# design.net
KiCad netlist of a schematic drawn in EasyEDA Pro
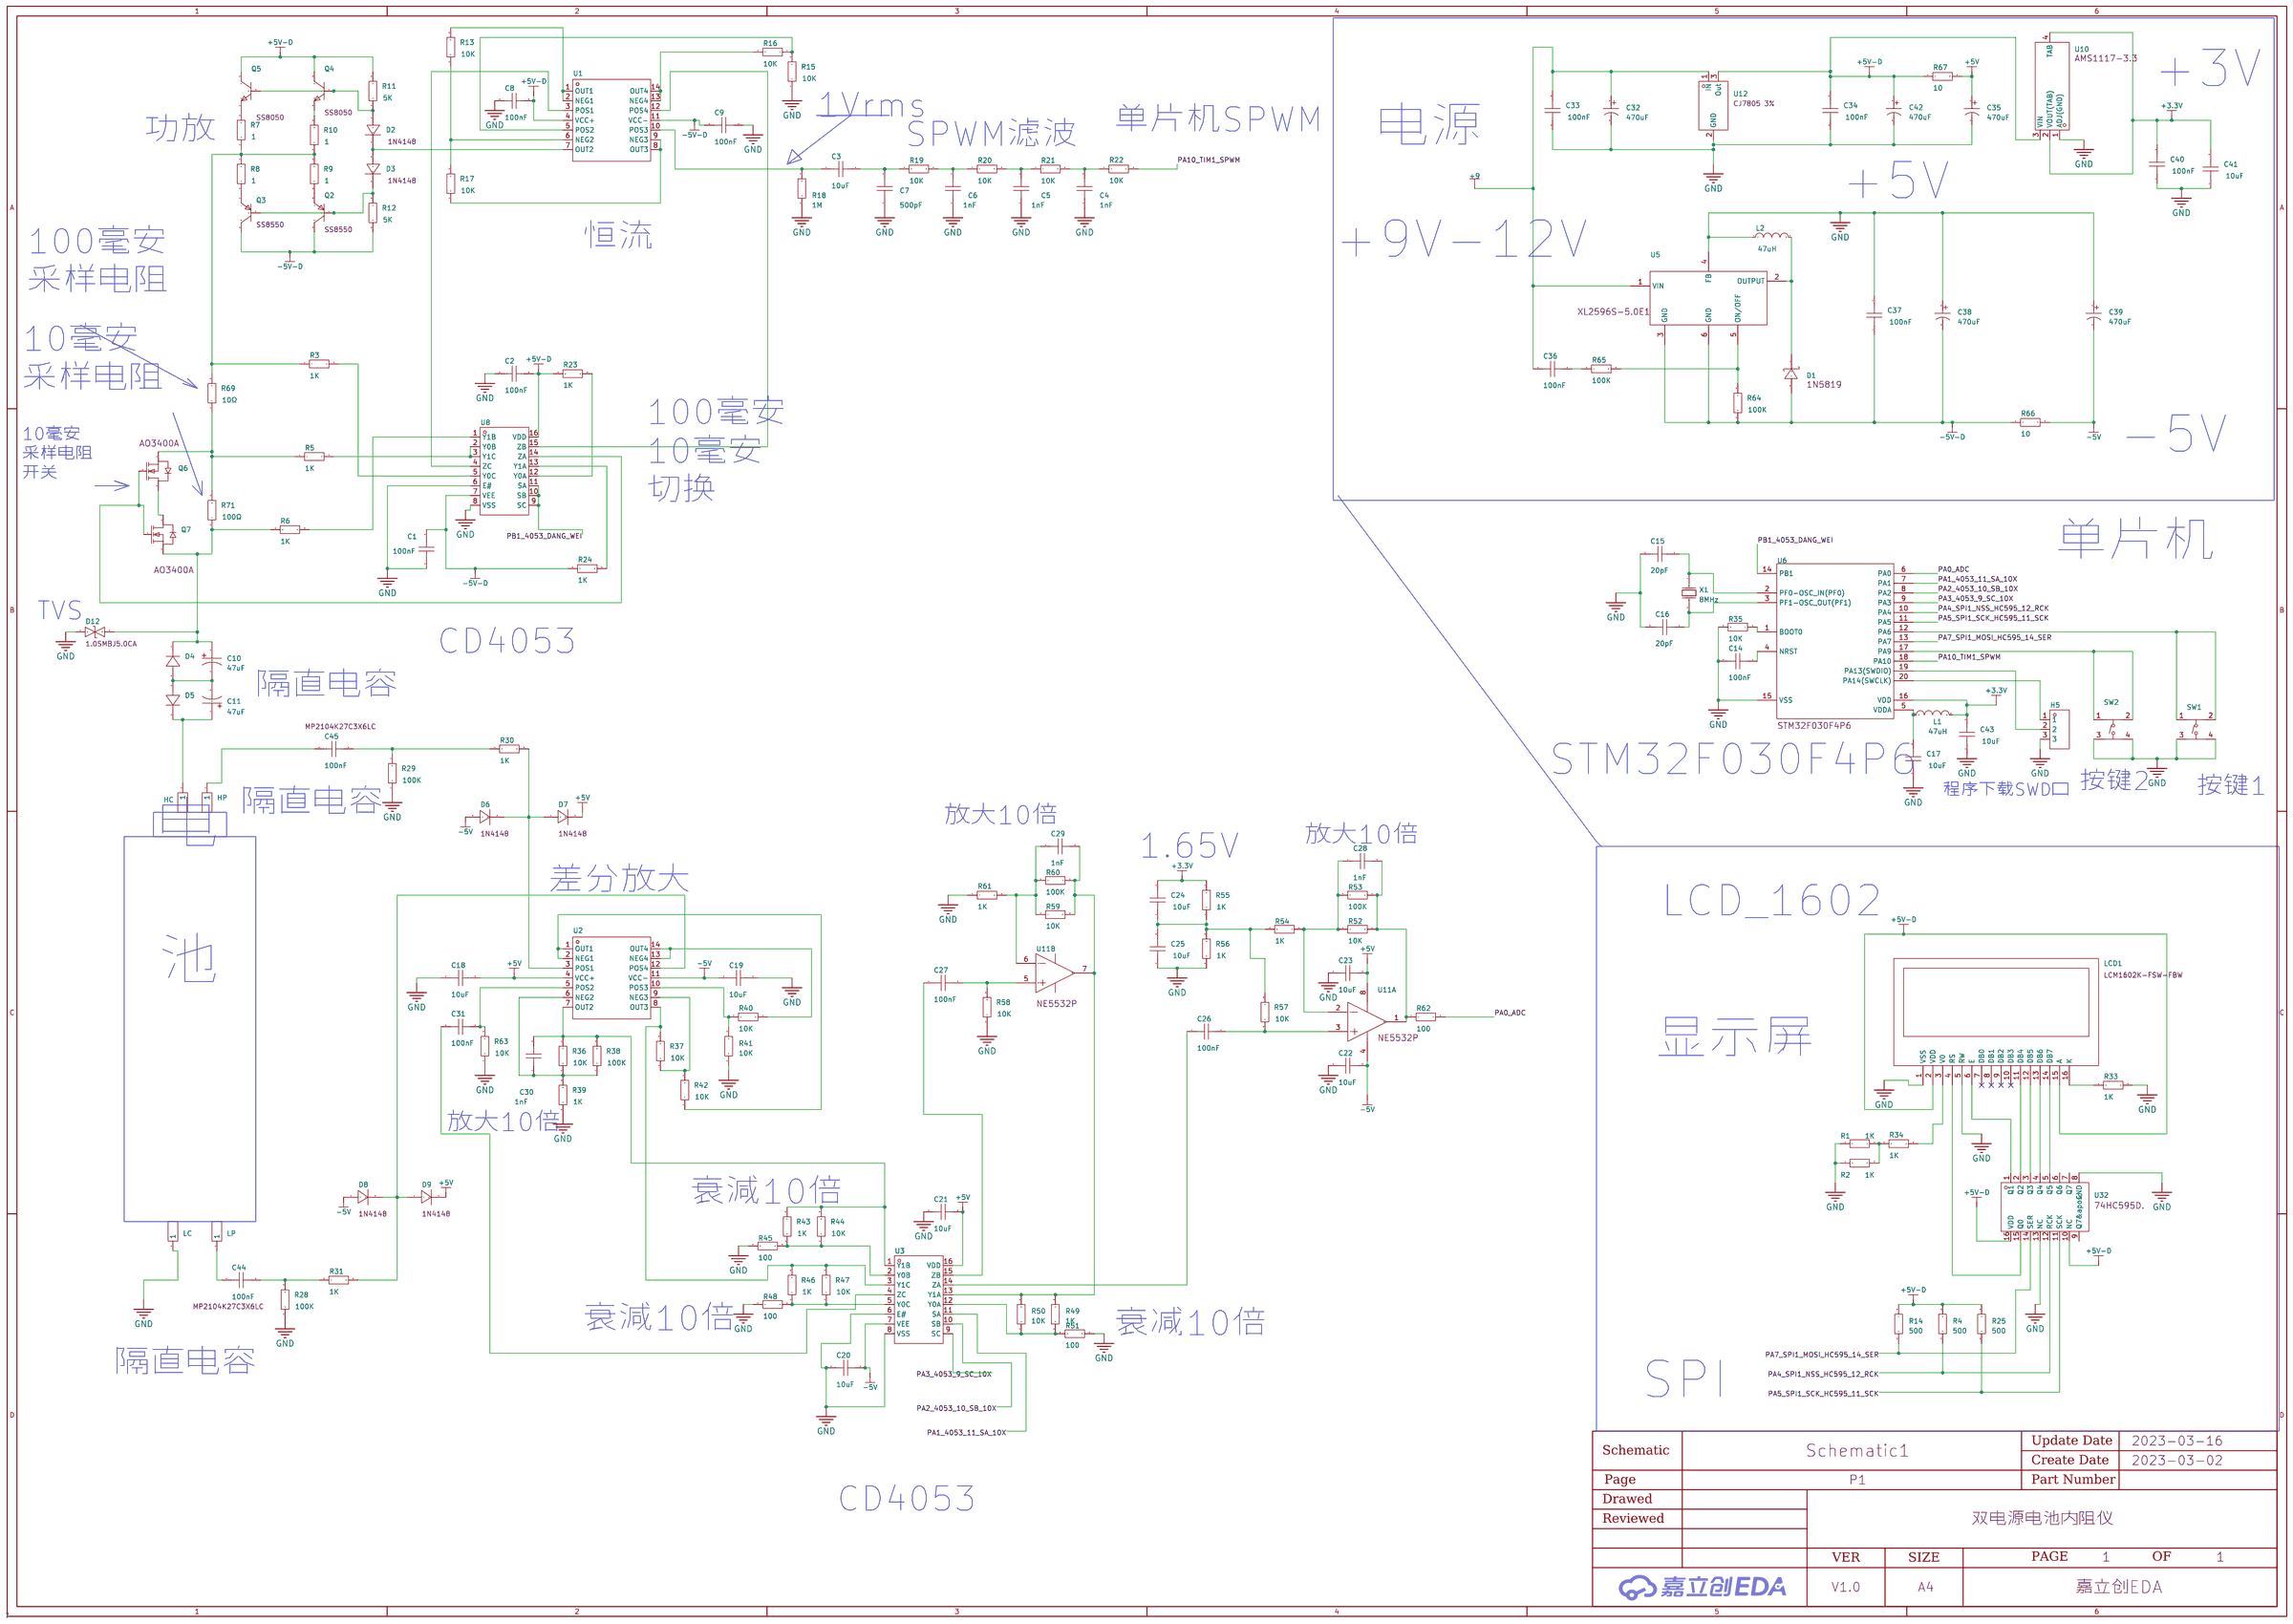
[diagram p0: schematic sheet]

(export (version "E")
  (design (tool "Eeschema 10.0.6"))
  (components
    (comp (ref "C1")
      (value "100nF")
      (footprint "easyedapro:C0603")
      (libsource (lib "easyedapro") (part "CapAcitance"))
    )
    (comp (ref "C2")
      (value "100nF")
      (footprint "easyedapro:C0603")
      (libsource (lib "easyedapro") (part "CapAcitance"))
    )
    (comp (ref "C3")
      (value "10uF")
      (footprint "easyedapro:C0603")
      (libsource (lib "easyedapro") (part "CapAcitance"))
    )
    (comp (ref "C4")
      (value "1nF")
      (footprint "easyedapro:C0603")
      (libsource (lib "easyedapro") (part "CapAcitance"))
    )
    (comp (ref "C5")
      (value "1nF")
      (footprint "easyedapro:C0603")
      (libsource (lib "easyedapro") (part "CapAcitance"))
    )
    (comp (ref "C6")
      (value "1nF")
      (footprint "easyedapro:C0603")
      (libsource (lib "easyedapro") (part "CapAcitance"))
    )
    (comp (ref "C7")
      (value "500pF")
      (footprint "easyedapro:C0603")
      (libsource (lib "easyedapro") (part "CapAcitance"))
    )
    (comp (ref "C8")
      (value "100nF")
      (footprint "easyedapro:C0603")
      (libsource (lib "easyedapro") (part "CapAcitance"))
    )
    (comp (ref "C9")
      (value "100nF")
      (footprint "easyedapro:C0603")
      (libsource (lib "easyedapro") (part "CapAcitance"))
    )
    (comp (ref "C10")
      (value "47uF")
      (footprint "easyedapro:CAP-TH_BD10.0-P5.00-D1.0-FD")
      (description "容值:47uF;精度:±20%;额定电压:200V;电容体直径:10mm;电容体长度:20mm;脚间距:5mm;工作寿命:5000hrs@105℃;")
      (fields (field (name "Manufacturer Part") "KF470M200G200A") (field (name "Manufacturer") "CapXon(丰宾)"))
      (libsource (lib "easyedapro") (part "KF470M200G200A"))
    )
    (comp (ref "C11")
      (value "47uF")
      (footprint "easyedapro:CAP-TH_BD10.0-P5.00-D1.0-FD")
      (description "容值:47uF;精度:±20%;额定电压:200V;电容体直径:10mm;电容体长度:20mm;脚间距:5mm;工作寿命:5000hrs@105℃;")
      (fields (field (name "Manufacturer Part") "KF470M200G200A") (field (name "Manufacturer") "CapXon(丰宾)"))
      (libsource (lib "easyedapro") (part "KF470M200G200A"))
    )
    (comp (ref "C14")
      (value "100nF")
      (footprint "easyedapro:C0603")
      (libsource (lib "easyedapro") (part "CapAcitance"))
    )
    (comp (ref "C15")
      (value "20pF")
      (footprint "easyedapro:C0603")
      (libsource (lib "easyedapro") (part "CapAcitance"))
    )
    (comp (ref "C16")
      (value "20pF")
      (footprint "easyedapro:C0603")
      (libsource (lib "easyedapro") (part "CapAcitance"))
    )
    (comp (ref "C17")
      (value "10uF")
      (footprint "easyedapro:C0603")
      (libsource (lib "easyedapro") (part "CapAcitance"))
    )
    (comp (ref "C18")
      (value "10uF")
      (footprint "easyedapro:C0603")
      (libsource (lib "easyedapro") (part "CapAcitance"))
    )
    (comp (ref "C19")
      (value "10uF")
      (footprint "easyedapro:C0603")
      (libsource (lib "easyedapro") (part "CapAcitance"))
    )
    (comp (ref "C20")
      (value "10uF")
      (footprint "easyedapro:C0603")
      (libsource (lib "easyedapro") (part "CapAcitance"))
    )
    (comp (ref "C21")
      (value "10uF")
      (footprint "easyedapro:C0603")
      (libsource (lib "easyedapro") (part "CapAcitance"))
    )
    (comp (ref "C22")
      (value "10uF")
      (footprint "easyedapro:C0603")
      (libsource (lib "easyedapro") (part "CapAcitance"))
    )
    (comp (ref "C23")
      (value "10uF")
      (footprint "easyedapro:C0603")
      (libsource (lib "easyedapro") (part "CapAcitance"))
    )
    (comp (ref "C24")
      (value "10uF")
      (footprint "easyedapro:C0603")
      (libsource (lib "easyedapro") (part "CapAcitance"))
    )
    (comp (ref "C25")
      (value "10uF")
      (footprint "easyedapro:C0603")
      (libsource (lib "easyedapro") (part "CapAcitance"))
    )
    (comp (ref "C26")
      (value "100nF")
      (footprint "easyedapro:C0603")
      (libsource (lib "easyedapro") (part "CapAcitance"))
    )
    (comp (ref "C27")
      (value "100nF")
      (footprint "easyedapro:C0603")
      (libsource (lib "easyedapro") (part "CapAcitance"))
    )
    (comp (ref "C28")
      (value "1nF")
      (footprint "easyedapro:C0603")
      (libsource (lib "easyedapro") (part "CapAcitance"))
    )
    (comp (ref "C29")
      (value "1nF")
      (footprint "easyedapro:C0603")
      (libsource (lib "easyedapro") (part "CapAcitance"))
    )
    (comp (ref "C30")
      (value "1nF")
      (footprint "easyedapro:C0603")
      (libsource (lib "easyedapro") (part "CapAcitance"))
    )
    (comp (ref "C31")
      (value "100nF")
      (footprint "easyedapro:C0603")
      (libsource (lib "easyedapro") (part "CapAcitance"))
    )
    (comp (ref "C32")
      (value "470uF")
      (footprint "easyedapro:CAP-TH_BD8.0-P3.50-D0.6-FD")
      (description "容值:470uF;精度:±20%;额定电压:16V;电容体直径:8mm;电容体长度:12mm;脚间距:3.5mm;工作寿命:2000hrs@105℃;")
      (fields
        (field (name "Manufacturer Part") "KM477M016F12RR0VH2FP0")
        (field (name "Manufacturer") "CX(承兴)")
      )
      (libsource (lib "easyedapro") (part "470uf16v"))
    )
    (comp (ref "C33")
      (value "100nF")
      (footprint "easyedapro:C0603")
      (libsource (lib "easyedapro") (part "CapAcitance"))
    )
    (comp (ref "C34")
      (value "100nF")
      (footprint "easyedapro:C0603")
      (libsource (lib "easyedapro") (part "CapAcitance"))
    )
    (comp (ref "C35")
      (value "470uF")
      (footprint "easyedapro:CAP-TH_BD8.0-P3.50-D0.6-FD")
      (description "容值:470uF;精度:±20%;额定电压:16V;电容体直径:8mm;电容体长度:12mm;脚间距:3.5mm;工作寿命:2000hrs@105℃;")
      (fields
        (field (name "Manufacturer Part") "KM477M016F12RR0VH2FP0")
        (field (name "Manufacturer") "CX(承兴)")
      )
      (libsource (lib "easyedapro") (part "470uf16v"))
    )
    (comp (ref "C36")
      (value "100nF")
      (footprint "easyedapro:C0603")
      (libsource (lib "easyedapro") (part "CapAcitance"))
    )
    (comp (ref "C37")
      (value "100nF")
      (footprint "easyedapro:C0603")
      (libsource (lib "easyedapro") (part "CapAcitance"))
    )
    (comp (ref "C38")
      (value "470uF")
      (footprint "easyedapro:CAP-TH_BD8.0-P3.50-D0.6-FD")
      (description "容值:470uF;精度:±20%;额定电压:16V;电容体直径:8mm;电容体长度:12mm;脚间距:3.5mm;工作寿命:2000hrs@105℃;")
      (fields
        (field (name "Manufacturer Part") "KM477M016F12RR0VH2FP0")
        (field (name "Manufacturer") "CX(承兴)")
      )
      (libsource (lib "easyedapro") (part "470uf16v"))
    )
    (comp (ref "C39")
      (value "470uF")
      (footprint "easyedapro:CAP-TH_BD8.0-P3.50-D0.6-FD")
      (description "容值:470uF;精度:±20%;额定电压:16V;电容体直径:8mm;电容体长度:12mm;脚间距:3.5mm;工作寿命:2000hrs@105℃;")
      (fields
        (field (name "Manufacturer Part") "KM477M016F12RR0VH2FP0")
        (field (name "Manufacturer") "CX(承兴)")
      )
      (libsource (lib "easyedapro") (part "470uf16v"))
    )
    (comp (ref "C40")
      (value "100nF")
      (footprint "easyedapro:C0603")
      (libsource (lib "easyedapro") (part "CapAcitance"))
    )
    (comp (ref "C41")
      (value "10uF")
      (footprint "easyedapro:C0603")
      (libsource (lib "easyedapro") (part "CapAcitance"))
    )
    (comp (ref "C42")
      (value "470uF")
      (footprint "easyedapro:CAP-TH_BD8.0-P3.50-D0.6-FD")
      (description "容值:470uF;精度:±20%;额定电压:16V;电容体直径:8mm;电容体长度:12mm;脚间距:3.5mm;工作寿命:2000hrs@105℃;")
      (fields
        (field (name "Manufacturer Part") "KM477M016F12RR0VH2FP0")
        (field (name "Manufacturer") "CX(承兴)")
      )
      (libsource (lib "easyedapro") (part "470uf16v"))
    )
    (comp (ref "C43")
      (value "10uF")
      (footprint "easyedapro:C0603")
      (libsource (lib "easyedapro") (part "CapAcitance"))
    )
    (comp (ref "C44")
      (value "100nF")
      (footprint "easyedapro:CAP-TH_L13.0-W6.0-P10.00-D1.0")
      (description "等级:X2;容值:100nF;精度:±10%;")
      (fields (field (name "Manufacturer Part") "MP2104K27C3X6LC") (field (name "Manufacturer") "SRD(圣融达)"))
      (libsource (lib "easyedapro") (part "MP2104KGC3XLC"))
    )
    (comp (ref "C45")
      (value "100nF")
      (footprint "easyedapro:CAP-TH_L13.0-W6.0-P10.00-D1.0")
      (description "等级:X2;容值:100nF;精度:±10%;")
      (fields (field (name "Manufacturer Part") "MP2104K27C3X6LC") (field (name "Manufacturer") "SRD(圣融达)"))
      (libsource (lib "easyedapro") (part "MP2104KGC3XLC"))
    )
    (comp (ref "D1")
      (value "1N5819")
      (footprint "easyedapro:SMA_L4.4-W2.6-LS5.0-RD")
      (description "直流反向耐压(Vr):40V;平均整流电流(Io):1A;正向压降(Vf):500mV@1A;")
      (fields (field (name "Manufacturer Part") "1N5819") (field (name "Manufacturer") "KEXIN(科信)"))
      (libsource (lib "easyedapro") (part "1N5819_C437199"))
    )
    (comp (ref "D2")
      (value "1N4148")
      (footprint "easyedapro:DO-35_BD2.0-L4.0-P8.00-D0.5-FD")
      (fields (field (name "Manufacturer Part") "1N4148") (field (name "Manufacturer") "ST(先科)"))
      (libsource (lib "easyedapro") (part "1N4148"))
    )
    (comp (ref "D3")
      (value "1N4148")
      (footprint "easyedapro:DO-35_BD2.0-L4.0-P8.00-D0.5-FD")
      (fields (field (name "Manufacturer Part") "1N4148") (field (name "Manufacturer") "ST(先科)"))
      (libsource (lib "easyedapro") (part "1N4148"))
    )
    (comp (ref "D4")
      (value "~")
      (footprint "easyedapro:DO_1N4007")
      (libsource (lib "easyedapro") (part "D_1N4007"))
    )
    (comp (ref "D5")
      (value "~")
      (footprint "easyedapro:DO_1N4007")
      (libsource (lib "easyedapro") (part "D_1N4007"))
    )
    (comp (ref "D6")
      (value "1N4148")
      (footprint "easyedapro:DO-35_BD2.0-L4.0-P8.00-D0.5-FD")
      (fields (field (name "Manufacturer Part") "1N4148") (field (name "Manufacturer") "ST(先科)"))
      (libsource (lib "easyedapro") (part "1N4148"))
    )
    (comp (ref "D7")
      (value "1N4148")
      (footprint "easyedapro:DO-35_BD2.0-L4.0-P8.00-D0.5-FD")
      (fields (field (name "Manufacturer Part") "1N4148") (field (name "Manufacturer") "ST(先科)"))
      (libsource (lib "easyedapro") (part "1N4148"))
    )
    (comp (ref "D8")
      (value "1N4148")
      (footprint "easyedapro:DO-35_BD2.0-L4.0-P8.00-D0.5-FD")
      (fields (field (name "Manufacturer Part") "1N4148") (field (name "Manufacturer") "ST(先科)"))
      (libsource (lib "easyedapro") (part "1N4148"))
    )
    (comp (ref "D9")
      (value "1N4148")
      (footprint "easyedapro:DO-35_BD2.0-L4.0-P8.00-D0.5-FD")
      (fields (field (name "Manufacturer Part") "1N4148") (field (name "Manufacturer") "ST(先科)"))
      (libsource (lib "easyedapro") (part "1N4148"))
    )
    (comp (ref "D12")
      (value "1.0SMBJ5.0CA")
      (footprint "easyedapro:SMB_L4.6-W3.6-LS5.3-BI")
      (description "极性:双向;反向截止电压(Vrwm):5V;击穿电压:6.4V;峰值脉冲电流(Ipp)@10/1000s:108.7A;最大钳位电压:9.2V;")
      (fields (field (name "Manufacturer Part") "1.0SMBJ5.0CA") (field (name "Manufacturer") "BORN(伯恩半导体)"))
      (libsource (lib "easyedapro") (part "1.0SMBJ5.0CA"))
    )
    (comp (ref "H5")
      (value "~")
      (footprint "easyedapro:HDR-TH_3P-P2.54-V-M")
      (libsource (lib "easyedapro") (part "PZ254V-11-03P_C2937625"))
    )
    (comp (ref "HC")
      (value "~")
      (footprint "easyedapro:HDR-TH_1P-V-M_XKB_X4611WV-01I-C28D40")
      (libsource (lib "easyedapro") (part "HDR_1x1"))
    )
    (comp (ref "HP")
      (value "~")
      (footprint "easyedapro:HDR-TH_1P-V-M_XKB_X4611WV-01I-C28D40")
      (libsource (lib "easyedapro") (part "HDR_1x1"))
    )
    (comp (ref "L1")
      (value "47uH")
      (footprint "easyedapro:IND-SMD_L4.5-W4.0_SLF0403")
      (description "电感值:47uH;直流电阻(DCR):844mΩ;精度:±10%;额定电流:540mA;")
      (fields
        (field (name "Manufacturer Part") "SLF0403-470KTT")
        (field (name "Manufacturer") "Sunltech(韩国顺磁)")
      )
      (libsource (lib "easyedapro") (part "SLF0403-470KTT"))
    )
    (comp (ref "L2")
      (value "47uH")
      (footprint "easyedapro:IND-SMD_L4.5-W4.0_SLF0403")
      (description "电感值:47uH;直流电阻(DCR):844mΩ;精度:±10%;额定电流:540mA;")
      (fields
        (field (name "Manufacturer Part") "SLF0403-470KTT")
        (field (name "Manufacturer") "Sunltech(韩国顺磁)")
      )
      (libsource (lib "easyedapro") (part "SLF0403-470KTT"))
    )
    (comp (ref "LC")
      (value "~")
      (footprint "easyedapro:HDR-TH_1P-V-M_XKB_X4611WV-01I-C28D40")
      (libsource (lib "easyedapro") (part "HDR_1x1"))
    )
    (comp (ref "LCD1")
      (value "LCM1602K-FSW-FBW")
      (footprint "easyedapro:MODULE-TH_LCM1602K")
      (description "尺寸(inch):-;主控芯片:KS0066U;")
      (fields
        (field (name "Manufacturer Part") "LCM1602K-FSW-FBW")
        (field (name "Manufacturer") "LONTECH(厦门龙特)")
      )
      (libsource (lib "easyedapro") (part "LCM1602K-FSW-FBW"))
    )
    (comp (ref "LP")
      (value "~")
      (footprint "easyedapro:HDR-TH_1P-V-M_XKB_X4611WV-01I-C28D40")
      (libsource (lib "easyedapro") (part "HDR_1x1"))
    )
    (comp (ref "Q2")
      (value "SS8550")
      (footprint "easyedapro:SOT-23-3_L2.9-W1.6-P1.90-LS2.8-BR")
      (fields (field (name "Manufacturer Part") "SS8550") (field (name "Manufacturer") "ElecSuper(静芯微）"))
      (libsource (lib "easyedapro") (part "SS8550_C5249677"))
    )
    (comp (ref "Q3")
      (value "SS8550")
      (footprint "easyedapro:SOT-23-3_L2.9-W1.6-P1.90-LS2.8-BR")
      (fields (field (name "Manufacturer Part") "SS8550") (field (name "Manufacturer") "ElecSuper(静芯微）"))
      (libsource (lib "easyedapro") (part "SS8550_C5249677"))
    )
    (comp (ref "Q4")
      (value "SS8050")
      (footprint "easyedapro:SOT-23-3_L2.9-W1.6-P1.90-LS2.8-BR")
      (fields (field (name "Manufacturer Part") "SS8050") (field (name "Manufacturer") "ElecSuper(静芯微）"))
      (libsource (lib "easyedapro") (part "SS8050_C5249676"))
    )
    (comp (ref "Q5")
      (value "SS8050")
      (footprint "easyedapro:SOT-23-3_L2.9-W1.6-P1.90-LS2.8-BR")
      (fields (field (name "Manufacturer Part") "SS8050") (field (name "Manufacturer") "ElecSuper(静芯微）"))
      (libsource (lib "easyedapro") (part "SS8050_C5249676"))
    )
    (comp (ref "Q6")
      (value "AO3400A")
      (footprint "easyedapro:SOT-23-3_L2.9-W1.3-P1.90-LS2.4-BR")
      (fields (field (name "Manufacturer Part") "AO3400A") (field (name "Manufacturer") "UMW(广东友台半导体)"))
      (libsource (lib "easyedapro") (part "AO3400A_C347475"))
    )
    (comp (ref "Q7")
      (value "AO3400A")
      (footprint "easyedapro:SOT-23-3_L2.9-W1.3-P1.90-LS2.4-BR")
      (fields (field (name "Manufacturer Part") "AO3400A") (field (name "Manufacturer") "UMW(广东友台半导体)"))
      (libsource (lib "easyedapro") (part "AO3400A_C347475"))
    )
    (comp (ref "R1")
      (value "1K")
      (footprint "easyedapro:Res_1/8W")
      (libsource (lib "easyedapro") (part "电阻"))
    )
    (comp (ref "R2")
      (value "1K")
      (footprint "easyedapro:Res_1/8W")
      (libsource (lib "easyedapro") (part "电阻"))
    )
    (comp (ref "R3")
      (value "1K")
      (footprint "easyedapro:Res_1/8W")
      (libsource (lib "easyedapro") (part "电阻"))
    )
    (comp (ref "R4")
      (value "500")
      (footprint "easyedapro:Res_1/8W")
      (libsource (lib "easyedapro") (part "电阻"))
    )
    (comp (ref "R5")
      (value "1K")
      (footprint "easyedapro:Res_1/8W")
      (libsource (lib "easyedapro") (part "电阻"))
    )
    (comp (ref "R6")
      (value "1K")
      (footprint "easyedapro:Res_1/8W")
      (libsource (lib "easyedapro") (part "电阻"))
    )
    (comp (ref "R7") (value "1") (footprint "easyedapro:Res_1/8W") (libsource (lib "easyedapro") (part "电阻")))
    (comp (ref "R8") (value "1") (footprint "easyedapro:Res_1/8W") (libsource (lib "easyedapro") (part "电阻")))
    (comp (ref "R9") (value "1") (footprint "easyedapro:Res_1/8W") (libsource (lib "easyedapro") (part "电阻")))
    (comp (ref "R10")
      (value "1")
      (footprint "easyedapro:Res_1/8W")
      (libsource (lib "easyedapro") (part "电阻"))
    )
    (comp (ref "R11")
      (value "5K")
      (footprint "easyedapro:Res_1/8W")
      (libsource (lib "easyedapro") (part "电阻"))
    )
    (comp (ref "R12")
      (value "5K")
      (footprint "easyedapro:Res_1/8W")
      (libsource (lib "easyedapro") (part "电阻"))
    )
    (comp (ref "R13")
      (value "10K")
      (footprint "easyedapro:Res_1/8W")
      (libsource (lib "easyedapro") (part "电阻"))
    )
    (comp (ref "R14")
      (value "500")
      (footprint "easyedapro:Res_1/8W")
      (libsource (lib "easyedapro") (part "电阻"))
    )
    (comp (ref "R15")
      (value "10K")
      (footprint "easyedapro:Res_1/8W")
      (libsource (lib "easyedapro") (part "电阻"))
    )
    (comp (ref "R16")
      (value "10K")
      (footprint "easyedapro:Res_1/8W")
      (libsource (lib "easyedapro") (part "电阻"))
    )
    (comp (ref "R17")
      (value "10K")
      (footprint "easyedapro:Res_1/8W")
      (libsource (lib "easyedapro") (part "电阻"))
    )
    (comp (ref "R18")
      (value "1M")
      (footprint "easyedapro:Res_1/8W")
      (libsource (lib "easyedapro") (part "电阻"))
    )
    (comp (ref "R19")
      (value "10K")
      (footprint "easyedapro:Res_1/8W")
      (libsource (lib "easyedapro") (part "电阻"))
    )
    (comp (ref "R20")
      (value "10K")
      (footprint "easyedapro:Res_1/8W")
      (libsource (lib "easyedapro") (part "电阻"))
    )
    (comp (ref "R21")
      (value "10K")
      (footprint "easyedapro:Res_1/8W")
      (libsource (lib "easyedapro") (part "电阻"))
    )
    (comp (ref "R22")
      (value "10K")
      (footprint "easyedapro:Res_1/8W")
      (libsource (lib "easyedapro") (part "电阻"))
    )
    (comp (ref "R23")
      (value "1K")
      (footprint "easyedapro:Res_1/8W")
      (libsource (lib "easyedapro") (part "电阻"))
    )
    (comp (ref "R24")
      (value "1K")
      (footprint "easyedapro:Res_1/8W")
      (libsource (lib "easyedapro") (part "电阻"))
    )
    (comp (ref "R25")
      (value "500")
      (footprint "easyedapro:Res_1/8W")
      (libsource (lib "easyedapro") (part "电阻"))
    )
    (comp (ref "R28")
      (value "100K")
      (footprint "easyedapro:Res_1/8W")
      (libsource (lib "easyedapro") (part "电阻"))
    )
    (comp (ref "R29")
      (value "100K")
      (footprint "easyedapro:Res_1/8W")
      (libsource (lib "easyedapro") (part "电阻"))
    )
    (comp (ref "R30")
      (value "1K")
      (footprint "easyedapro:Res_1/8W")
      (libsource (lib "easyedapro") (part "电阻"))
    )
    (comp (ref "R31")
      (value "1K")
      (footprint "easyedapro:Res_1/8W")
      (libsource (lib "easyedapro") (part "电阻"))
    )
    (comp (ref "R33")
      (value "1K")
      (footprint "easyedapro:Res_1/8W")
      (libsource (lib "easyedapro") (part "电阻"))
    )
    (comp (ref "R34")
      (value "1K")
      (footprint "easyedapro:Res_1/8W")
      (libsource (lib "easyedapro") (part "电阻"))
    )
    (comp (ref "R35")
      (value "10K")
      (footprint "easyedapro:Res_1/8W")
      (libsource (lib "easyedapro") (part "电阻"))
    )
    (comp (ref "R36")
      (value "10K")
      (footprint "easyedapro:Res_1/8W")
      (libsource (lib "easyedapro") (part "电阻"))
    )
    (comp (ref "R37")
      (value "10K")
      (footprint "easyedapro:Res_1/8W")
      (libsource (lib "easyedapro") (part "电阻"))
    )
    (comp (ref "R38")
      (value "100K")
      (footprint "easyedapro:Res_1/8W")
      (libsource (lib "easyedapro") (part "电阻"))
    )
    (comp (ref "R39")
      (value "1K")
      (footprint "easyedapro:Res_1/8W")
      (libsource (lib "easyedapro") (part "电阻"))
    )
    (comp (ref "R40")
      (value "10K")
      (footprint "easyedapro:Res_1/8W")
      (libsource (lib "easyedapro") (part "电阻"))
    )
    (comp (ref "R41")
      (value "10K")
      (footprint "easyedapro:Res_1/8W")
      (libsource (lib "easyedapro") (part "电阻"))
    )
    (comp (ref "R42")
      (value "10K")
      (footprint "easyedapro:Res_1/8W")
      (libsource (lib "easyedapro") (part "电阻"))
    )
    (comp (ref "R43")
      (value "1K")
      (footprint "easyedapro:Res_1/8W")
      (libsource (lib "easyedapro") (part "电阻"))
    )
    (comp (ref "R44")
      (value "10K")
      (footprint "easyedapro:Res_1/8W")
      (libsource (lib "easyedapro") (part "电阻"))
    )
    (comp (ref "R45")
      (value "100")
      (footprint "easyedapro:Res_1/8W")
      (libsource (lib "easyedapro") (part "电阻"))
    )
    (comp (ref "R46")
      (value "1K")
      (footprint "easyedapro:Res_1/8W")
      (libsource (lib "easyedapro") (part "电阻"))
    )
    (comp (ref "R47")
      (value "10K")
      (footprint "easyedapro:Res_1/8W")
      (libsource (lib "easyedapro") (part "电阻"))
    )
    (comp (ref "R48")
      (value "100")
      (footprint "easyedapro:Res_1/8W")
      (libsource (lib "easyedapro") (part "电阻"))
    )
    (comp (ref "R49")
      (value "1K")
      (footprint "easyedapro:Res_1/8W")
      (libsource (lib "easyedapro") (part "电阻"))
    )
    (comp (ref "R50")
      (value "10K")
      (footprint "easyedapro:Res_1/8W")
      (libsource (lib "easyedapro") (part "电阻"))
    )
    (comp (ref "R51")
      (value "100")
      (footprint "easyedapro:Res_1/8W")
      (libsource (lib "easyedapro") (part "电阻"))
    )
    (comp (ref "R52")
      (value "10K")
      (footprint "easyedapro:Res_1/8W")
      (libsource (lib "easyedapro") (part "电阻"))
    )
    (comp (ref "R53")
      (value "100K")
      (footprint "easyedapro:Res_1/8W")
      (libsource (lib "easyedapro") (part "电阻"))
    )
    (comp (ref "R54")
      (value "1K")
      (footprint "easyedapro:Res_1/8W")
      (libsource (lib "easyedapro") (part "电阻"))
    )
    (comp (ref "R55")
      (value "1K")
      (footprint "easyedapro:Res_1/8W")
      (libsource (lib "easyedapro") (part "电阻"))
    )
    (comp (ref "R56")
      (value "1K")
      (footprint "easyedapro:Res_1/8W")
      (libsource (lib "easyedapro") (part "电阻"))
    )
    (comp (ref "R57")
      (value "10K")
      (footprint "easyedapro:Res_1/8W")
      (libsource (lib "easyedapro") (part "电阻"))
    )
    (comp (ref "R58")
      (value "10K")
      (footprint "easyedapro:Res_1/8W")
      (libsource (lib "easyedapro") (part "电阻"))
    )
    (comp (ref "R59")
      (value "10K")
      (footprint "easyedapro:Res_1/8W")
      (libsource (lib "easyedapro") (part "电阻"))
    )
    (comp (ref "R60")
      (value "100K")
      (footprint "easyedapro:Res_1/8W")
      (libsource (lib "easyedapro") (part "电阻"))
    )
    (comp (ref "R61")
      (value "1K")
      (footprint "easyedapro:Res_1/8W")
      (libsource (lib "easyedapro") (part "电阻"))
    )
    (comp (ref "R62")
      (value "100")
      (footprint "easyedapro:Res_1/8W")
      (libsource (lib "easyedapro") (part "电阻"))
    )
    (comp (ref "R63")
      (value "10K")
      (footprint "easyedapro:Res_1/8W")
      (libsource (lib "easyedapro") (part "电阻"))
    )
    (comp (ref "R64")
      (value "100K")
      (footprint "easyedapro:Res_1/8W")
      (libsource (lib "easyedapro") (part "电阻"))
    )
    (comp (ref "R65")
      (value "100K")
      (footprint "easyedapro:Res_1/8W")
      (libsource (lib "easyedapro") (part "电阻"))
    )
    (comp (ref "R66") (value "10") (footprint "easyedapro:R0603") (libsource (lib "easyedapro") (part "电阻")))
    (comp (ref "R67") (value "10") (footprint "easyedapro:R0603") (libsource (lib "easyedapro") (part "电阻")))
    (comp (ref "R69")
      (value "10Ω")
      (footprint "easyedapro:R2512")
      (description "电阻类型:厚膜电阻;阻值:10Ω;精度:±5%;功率:2W;温度系数:±200ppm/℃;最大工作电压:200V;工作温度范围:-55℃~+155℃;")
      (fields (field (name "Manufacturer Part") "RC2512JK-7W10RL") (field (name "Manufacturer") "YAGEO(国巨)"))
      (libsource (lib "easyedapro") (part "RC2512JK-7W10RL"))
    )
    (comp (ref "R71")
      (value "100Ω")
      (footprint "easyedapro:R0603")
      (description "电阻类型:厚膜电阻;阻值:100Ω;精度:±1%;功率:100mW;温度系数:±100ppm/℃;最大工作电压:75V;工作温度范围:-55℃~+155℃;")
      (fields (field (name "Manufacturer Part") "AC0603FR-07100RL") (field (name "Manufacturer") "YAGEO(国巨)"))
      (libsource (lib "easyedapro") (part "AC0603FR-07100RL"))
    )
    (comp (ref "SW1")
      (value "1TS005A-2600-5001")
      (footprint "easyedapro:SW-TH_4P-L6.0-W6.0-P4.50-LS6.5")
      (fields (field (name "Manufacturer") "HYP(鸿源精密)"))
      (libsource (lib "easyedapro") (part "1TS005A-2600-5001"))
    )
    (comp (ref "SW2")
      (value "1TS005A-2600-5001")
      (footprint "easyedapro:SW-TH_4P-L6.0-W6.0-P4.50-LS6.5")
      (fields (field (name "Manufacturer") "HYP(鸿源精密)"))
      (libsource (lib "easyedapro") (part "1TS005A-2600-5001"))
    )
    (comp (ref "U1")
      (value "TL084CN")
      (footprint "easyedapro:DIP-14_L17.8-W10.2-P2.54-BL")
      (description "运放类型:J-FET;放大器组数:4;增益带宽积（GBP）:4MHz;压摆率（SR）:16 V/us;电源电压:6V ~ 36V, ±3V ~ 18V;各通道供电电流:1.4mA;")
      (fields (field (name "Manufacturer") "TI(德州仪器)"))
      (libsource (lib "easyedapro") (part "TL084CN_C54501"))
    )
    (comp (ref "U2")
      (value "TL084CN")
      (footprint "easyedapro:DIP-14_L17.8-W10.2-P2.54-BL")
      (description "运放类型:J-FET;放大器组数:4;增益带宽积（GBP）:4MHz;压摆率（SR）:16 V/us;电源电压:6V ~ 36V, ±3V ~ 18V;各通道供电电流:1.4mA;")
      (fields (field (name "Manufacturer") "TI(德州仪器)"))
      (libsource (lib "easyedapro") (part "TL084CN_C54501"))
    )
    (comp (ref "U3")
      (value "CD4053BM/TR")
      (footprint "easyedapro:SOP-16_L9.9-W3.9-P1.27-LS6.1-BL")
      (fields (field (name "Manufacturer") "HGSEMI(华冠)"))
      (libsource (lib "easyedapro") (part "CD4053BM/TR"))
    )
    (comp (ref "U5")
      (value "XL2596S-5.0E1")
      (footprint "easyedapro:TO-263-5_L10.2-W9.9-P1.70-LS14.4-TL")
      (fields (field (name "Manufacturer Part") "XL2596S-5.0E1") (field (name "Manufacturer") "XLSEMI(芯龙)"))
      (libsource (lib "easyedapro") (part "XL2596S-5.0E1"))
    )
    (comp (ref "U6")
      (value "STM32F030F4P6")
      (footprint "easyedapro:TSSOP-20_L6.5-W4.4-P0.65-LS6.4-BL")
      (fields (field (name "Manufacturer Part") "STM32F030F4P6") (field (name "Manufacturer") "ST(意法半导体)"))
      (libsource (lib "easyedapro") (part "STM32F030F4P6"))
    )
    (comp (ref "U8")
      (value "CD4053BM/TR")
      (footprint "easyedapro:SOP-16_L9.9-W3.9-P1.27-LS6.1-BL")
      (fields (field (name "Manufacturer") "HGSEMI(华冠)"))
      (libsource (lib "easyedapro") (part "CD4053BM/TR"))
    )
    (comp (ref "U10")
      (value "AMS1117-3.3")
      (footprint "easyedapro:SOT-223-4_L6.5-W3.5-P2.30-LS7.0-BR")
      (description "输出类型:固定;输出极性:正;输出通道数:1;最大输入电压:18V;输出电压:3.3V;压差:1.3V@(1A);输出电流:1A;电源纹波抑制比(PSRR):60dB@(120Hz);")
      (fields (field (name "Manufacturer Part") "AMS1117-3.3") (field (name "Manufacturer") "UMW(广东友台半导体)"))
      (libsource (lib "easyedapro") (part "AMS1117-3.3_C347222"))
    )
    (comp (ref "U11")
      (value "NE5532P")
      (footprint "easyedapro:DIP-8_L9.4-W6.4-P2.54-LS9.1-BL")
      (description "运放类型:General Purpose;放大器组数:2;增益带宽积（GBP）:10MHz;压摆率（SR）:9 V/us;电源电压:±5V ~ 15V;各通道供电电流:8mA;")
      (fields (field (name "Manufacturer Part") "NE5532P") (field (name "Manufacturer") "TI(德州仪器)"))
      (libsource (lib "easyedapro") (part "NE5532P"))
    )
    (comp (ref "U12")
      (value "CJ7805 3%")
      (footprint "easyedapro:TO-252-2_L6.6-W6.1-P4.58-LS10.1-BR-CW")
      (description "输出类型:固定;输出极性:正;输出通道数:1;最大输入电压:35V;输出电压:5V;压差:2V@(1A);输出电流:1.5A;")
      (fields (field (name "Manufacturer Part") "CJ7805 3%") (field (name "Manufacturer") "CJ(江苏长电/长晶)"))
      (libsource (lib "easyedapro") (part "CJ7805 3%"))
    )
    (comp (ref "U32")
      (value "74HC595D.")
      (footprint "easyedapro:SOP-16_L9.9-W3.9-P1.27-LS6.0-BL")
      (fields (field (name "Manufacturer Part") "74HC595D.") (field (name "Manufacturer") "FM(富满)"))
      (libsource (lib "easyedapro") (part "74HC595D."))
    )
    (comp (ref "X1")
      (value "8MHz")
      (footprint "easyedapro:OSC-TH_L10.0-W4.5-P5.00")
      (description "晶振类型:49S晶振;频率:8MHz;频率公差:±20ppm;频率稳定度:±30ppm;负载电容:20pF;工作温度:-20℃~+70℃;")
      (fields (field (name "Manufacturer Part") "X49SD8MSD2SC") (field (name "Manufacturer") "YXC(扬兴晶振)"))
      (libsource (lib "easyedapro") (part "X49SD8MSD2SC"))
    )
  )
  (nets
    (net (code "1") (name "+3.3V") (class "Default")
      (node (ref "C24") (pin "2") (pinfunction "2_2") (pintype "input"))
      (node (ref "C40") (pin "2") (pinfunction "2_2") (pintype "input"))
      (node (ref "C41") (pin "2") (pinfunction "2_2") (pintype "input"))
      (node (ref "C43") (pin "2") (pinfunction "2_2") (pintype "input"))
      (node (ref "L1") (pin "2") (pinfunction "2_2") (pintype "input"))
      (node (ref "R55") (pin "2") (pinfunction "2_2") (pintype "input"))
      (node (ref "U10") (pin "2") (pinfunction "VOUT(TAB)_2") (pintype "input"))
      (node (ref "U10") (pin "4") (pinfunction "TAB_4") (pintype "input"))
      (node (ref "U6") (pin "16") (pinfunction "VDD_16") (pintype "input"))
    )
    (net (code "2") (name "+5V") (class "Default")
      (node (ref "C18") (pin "2") (pinfunction "2_2") (pintype "input"))
      (node (ref "C21") (pin "2") (pinfunction "2_2") (pintype "input"))
      (node (ref "C23") (pin "2") (pinfunction "2_2") (pintype "input"))
      (node (ref "C35") (pin "1") (pinfunction "1_1") (pintype "input"))
      (node (ref "D7") (pin "2") (pinfunction "C_2") (pintype "input"))
      (node (ref "D9") (pin "2") (pinfunction "C_2") (pintype "input"))
      (node (ref "R67") (pin "2") (pinfunction "2_2") (pintype "input"))
      (node (ref "U11") (pin "8") (pinfunction "VCC+_8") (pintype "input"))
      (node (ref "U2") (pin "4") (pinfunction "VCC+_4") (pintype "input"))
      (node (ref "U3") (pin "16") (pinfunction "VDD_16") (pintype "input"))
    )
    (net (code "3") (name "+5V-D") (class "Default")
      (node (ref "C2") (pin "2") (pinfunction "2_2") (pintype "input"))
      (node (ref "C34") (pin "2") (pinfunction "2_2") (pintype "input"))
      (node (ref "C42") (pin "1") (pinfunction "1_1") (pintype "input"))
      (node (ref "C8") (pin "2") (pinfunction "2_2") (pintype "input"))
      (node (ref "LCD1") (pin "15") (pinfunction "A_15") (pintype "input"))
      (node (ref "LCD1") (pin "2") (pinfunction "VDD_2") (pintype "input"))
      (node (ref "Q4") (pin "3") (pinfunction "C_3") (pintype "input"))
      (node (ref "Q5") (pin "3") (pinfunction "C_3") (pintype "input"))
      (node (ref "R11") (pin "2") (pinfunction "2_2") (pintype "input"))
      (node (ref "R14") (pin "2") (pinfunction "2_2") (pintype "input"))
      (node (ref "R23") (pin "1") (pinfunction "1_1") (pintype "input"))
      (node (ref "R25") (pin "2") (pinfunction "2_2") (pintype "input"))
      (node (ref "R4") (pin "2") (pinfunction "2_2") (pintype "input"))
      (node (ref "R67") (pin "1") (pinfunction "1_1") (pintype "input"))
      (node (ref "U1") (pin "4") (pinfunction "VCC+_4") (pintype "input"))
      (node (ref "U10") (pin "3") (pinfunction "VIN_3") (pintype "input"))
      (node (ref "U12") (pin "3") (pinfunction "Out_3") (pintype "input"))
      (node (ref "U32") (pin "10") (pinfunction "NC_10") (pintype "input"))
      (node (ref "U32") (pin "16") (pinfunction "VDD_16") (pintype "input"))
      (node (ref "U8") (pin "16") (pinfunction "VDD_16") (pintype "input"))
    )
    (net (code "4") (name "+9") (class "Default")
      (node (ref "C32") (pin "1") (pinfunction "1_1") (pintype "input"))
      (node (ref "C33") (pin "2") (pinfunction "2_2") (pintype "input"))
      (node (ref "C36") (pin "1") (pinfunction "1_1") (pintype "input"))
      (node (ref "U12") (pin "1") (pinfunction "IN_1") (pintype "input"))
      (node (ref "U5") (pin "1") (pinfunction "VIN_1") (pintype "input"))
    )
    (net (code "5") (name "-5V") (class "Default")
      (node (ref "C19") (pin "1") (pinfunction "1_1") (pintype "input"))
      (node (ref "C20") (pin "2") (pinfunction "2_2") (pintype "input"))
      (node (ref "C22") (pin "2") (pinfunction "2_2") (pintype "input"))
      (node (ref "C39") (pin "2") (pinfunction "2_2") (pintype "input"))
      (node (ref "D6") (pin "1") (pinfunction "A_1") (pintype "input"))
      (node (ref "D8") (pin "1") (pinfunction "A_1") (pintype "input"))
      (node (ref "R66") (pin "2") (pinfunction "2_2") (pintype "input"))
      (node (ref "U11") (pin "4") (pinfunction "VCC-_4") (pintype "input"))
      (node (ref "U2") (pin "11") (pinfunction "VCC-_11") (pintype "input"))
      (node (ref "U3") (pin "7") (pinfunction "VEE_7") (pintype "input"))
    )
    (net (code "6") (name "-5V-D") (class "Default")
      (node (ref "C1") (pin "2") (pinfunction "2_2") (pintype "input"))
      (node (ref "C37") (pin "1") (pinfunction "1_1") (pintype "input"))
      (node (ref "C38") (pin "2") (pinfunction "2_2") (pintype "input"))
      (node (ref "C9") (pin "1") (pinfunction "1_1") (pintype "input"))
      (node (ref "D1") (pin "2") (pinfunction "A_2") (pintype "input"))
      (node (ref "Q2") (pin "3") (pinfunction "C_3") (pintype "input"))
      (node (ref "Q3") (pin "3") (pinfunction "C_3") (pintype "input"))
      (node (ref "R12") (pin "1") (pinfunction "1_1") (pintype "input"))
      (node (ref "R24") (pin "1") (pinfunction "1_1") (pintype "input"))
      (node (ref "R64") (pin "1") (pinfunction "1_1") (pintype "input"))
      (node (ref "R66") (pin "1") (pinfunction "1_1") (pintype "input"))
      (node (ref "U1") (pin "11") (pinfunction "VCC-_11") (pintype "input"))
      (node (ref "U5") (pin "3") (pinfunction "GND_3") (pintype "input"))
      (node (ref "U5") (pin "6") (pinfunction "GND_6") (pintype "input"))
      (node (ref "U8") (pin "7") (pinfunction "VEE_7") (pintype "input"))
    )
    (net (code "7") (name "/PA0_ADC") (class "Default")
      (node (ref "R62") (pin "2") (pinfunction "2_2") (pintype "input"))
      (node (ref "U6") (pin "6") (pinfunction "PA0_6") (pintype "bidirectional"))
    )
    (net (code "8") (name "/PA1_4053_11_SA_10X") (class "Default")
      (node (ref "U3") (pin "11") (pinfunction "SA_11") (pintype "input"))
      (node (ref "U6") (pin "7") (pinfunction "PA1_7") (pintype "bidirectional"))
    )
    (net (code "9") (name "/PA2_4053_10_SB_10X") (class "Default")
      (node (ref "U3") (pin "10") (pinfunction "SB_10") (pintype "input"))
      (node (ref "U6") (pin "8") (pinfunction "PA2_8") (pintype "bidirectional"))
    )
    (net (code "10") (name "/PA3_4053_9_SC_10X") (class "Default")
      (node (ref "U3") (pin "9") (pinfunction "SC_9") (pintype "input"))
      (node (ref "U6") (pin "9") (pinfunction "PA3_9") (pintype "bidirectional"))
    )
    (net (code "11") (name "/PA4_SPI1_NSS_HC595_12_RCK") (class "Default")
      (node (ref "R4") (pin "1") (pinfunction "1_1") (pintype "input"))
      (node (ref "U32") (pin "12") (pinfunction "RCK_12") (pintype "input"))
      (node (ref "U6") (pin "10") (pinfunction "PA4_10") (pintype "bidirectional"))
    )
    (net (code "12") (name "/PA5_SPI1_SCK_HC595_11_SCK") (class "Default")
      (node (ref "R25") (pin "1") (pinfunction "1_1") (pintype "input"))
      (node (ref "U32") (pin "11") (pinfunction "SCK_11") (pintype "input"))
      (node (ref "U6") (pin "11") (pinfunction "PA5_11") (pintype "bidirectional"))
    )
    (net (code "13") (name "/PA7_SPI1_MOSI_HC595_14_SER") (class "Default")
      (node (ref "R14") (pin "1") (pinfunction "1_1") (pintype "input"))
      (node (ref "U32") (pin "14") (pinfunction "SER_14") (pintype "input"))
      (node (ref "U6") (pin "13") (pinfunction "PA7_13") (pintype "bidirectional"))
    )
    (net (code "14") (name "/PA10_TIM1_SPWM") (class "Default")
      (node (ref "R22") (pin "2") (pinfunction "2_2") (pintype "input"))
      (node (ref "U6") (pin "18") (pinfunction "PA10_18") (pintype "bidirectional"))
    )
    (net (code "15") (name "/PB1_4053_DANG_WEI") (class "Default")
      (node (ref "U6") (pin "14") (pinfunction "PB1_14") (pintype "bidirectional"))
      (node (ref "U8") (pin "10") (pinfunction "SB_10") (pintype "input"))
      (node (ref "U8") (pin "11") (pinfunction "SA_11") (pintype "input"))
      (node (ref "U8") (pin "9") (pinfunction "SC_9") (pintype "input"))
    )
    (net (code "16") (name "GND") (class "Default")
      (node (ref "C1") (pin "1") (pinfunction "1_1") (pintype "input"))
      (node (ref "C14") (pin "2") (pinfunction "2_2") (pintype "input"))
      (node (ref "C15") (pin "2") (pinfunction "2_2") (pintype "input"))
      (node (ref "C16") (pin "2") (pinfunction "2_2") (pintype "input"))
      (node (ref "C17") (pin "1") (pinfunction "1_1") (pintype "input"))
      (node (ref "C18") (pin "1") (pinfunction "1_1") (pintype "input"))
      (node (ref "C19") (pin "2") (pinfunction "2_2") (pintype "input"))
      (node (ref "C2") (pin "1") (pinfunction "1_1") (pintype "input"))
      (node (ref "C20") (pin "1") (pinfunction "1_1") (pintype "input"))
      (node (ref "C21") (pin "1") (pinfunction "1_1") (pintype "input"))
      (node (ref "C22") (pin "1") (pinfunction "1_1") (pintype "input"))
      (node (ref "C23") (pin "1") (pinfunction "1_1") (pintype "input"))
      (node (ref "C25") (pin "1") (pinfunction "1_1") (pintype "input"))
      (node (ref "C32") (pin "2") (pinfunction "2_2") (pintype "input"))
      (node (ref "C33") (pin "1") (pinfunction "1_1") (pintype "input"))
      (node (ref "C34") (pin "1") (pinfunction "1_1") (pintype "input"))
      (node (ref "C35") (pin "2") (pinfunction "2_2") (pintype "input"))
      (node (ref "C37") (pin "2") (pinfunction "2_2") (pintype "input"))
      (node (ref "C38") (pin "1") (pinfunction "1_1") (pintype "input"))
      (node (ref "C39") (pin "1") (pinfunction "1_1") (pintype "input"))
      (node (ref "C4") (pin "1") (pinfunction "1_1") (pintype "input"))
      (node (ref "C40") (pin "1") (pinfunction "1_1") (pintype "input"))
      (node (ref "C41") (pin "1") (pinfunction "1_1") (pintype "input"))
      (node (ref "C42") (pin "2") (pinfunction "2_2") (pintype "input"))
      (node (ref "C43") (pin "1") (pinfunction "1_1") (pintype "input"))
      (node (ref "C5") (pin "1") (pinfunction "1_1") (pintype "input"))
      (node (ref "C6") (pin "1") (pinfunction "1_1") (pintype "input"))
      (node (ref "C7") (pin "1") (pinfunction "1_1") (pintype "input"))
      (node (ref "C8") (pin "1") (pinfunction "1_1") (pintype "input"))
      (node (ref "C9") (pin "2") (pinfunction "2_2") (pintype "input"))
      (node (ref "D12") (pin "1") (pinfunction "1_1") (pintype "input"))
      (node (ref "H5") (pin "3") (pinfunction "3_3") (pintype "input"))
      (node (ref "L2") (pin "1") (pinfunction "1_1") (pintype "input"))
      (node (ref "LC") (pin "1") (pinfunction "1_1") (pintype "unspecified"))
      (node (ref "LCD1") (pin "1") (pinfunction "VSS_1") (pintype "input"))
      (node (ref "LCD1") (pin "5") (pinfunction "RW_5") (pintype "input"))
      (node (ref "R1") (pin "1") (pinfunction "1_1") (pintype "input"))
      (node (ref "R15") (pin "1") (pinfunction "1_1") (pintype "input"))
      (node (ref "R18") (pin "1") (pinfunction "1_1") (pintype "input"))
      (node (ref "R2") (pin "1") (pinfunction "1_1") (pintype "input"))
      (node (ref "R28") (pin "1") (pinfunction "1_1") (pintype "input"))
      (node (ref "R29") (pin "1") (pinfunction "1_1") (pintype "input"))
      (node (ref "R33") (pin "2") (pinfunction "2_2") (pintype "input"))
      (node (ref "R35") (pin "2") (pinfunction "2_2") (pintype "input"))
      (node (ref "R39") (pin "1") (pinfunction "1_1") (pintype "input"))
      (node (ref "R41") (pin "1") (pinfunction "1_1") (pintype "input"))
      (node (ref "R45") (pin "1") (pinfunction "1_1") (pintype "input"))
      (node (ref "R48") (pin "1") (pinfunction "1_1") (pintype "input"))
      (node (ref "R51") (pin "1") (pinfunction "1_1") (pintype "input"))
      (node (ref "R56") (pin "1") (pinfunction "1_1") (pintype "input"))
      (node (ref "R58") (pin "1") (pinfunction "1_1") (pintype "input"))
      (node (ref "R61") (pin "1") (pinfunction "1_1") (pintype "input"))
      (node (ref "R63") (pin "1") (pinfunction "1_1") (pintype "input"))
      (node (ref "SW1") (pin "3") (pinfunction "3_3") (pintype "input"))
      (node (ref "SW1") (pin "4") (pinfunction "4_4") (pintype "input"))
      (node (ref "SW2") (pin "3") (pinfunction "3_3") (pintype "input"))
      (node (ref "SW2") (pin "4") (pinfunction "4_4") (pintype "input"))
      (node (ref "U10") (pin "1") (pinfunction "ADJ(GND)_1") (pintype "input"))
      (node (ref "U12") (pin "2") (pinfunction "GND_2") (pintype "input"))
      (node (ref "U3") (pin "6") (pinfunction "E#_6") (pintype "input"))
      (node (ref "U3") (pin "8") (pinfunction "VSS_8") (pintype "input"))
      (node (ref "U32") (pin "13") (pinfunction "NC_13") (pintype "input"))
      (node (ref "U32") (pin "8") (pinfunction "GND_8") (pintype "input"))
      (node (ref "U5") (pin "4") (pinfunction "FB_4") (pintype "input"))
      (node (ref "U6") (pin "15") (pinfunction "VSS_15") (pintype "input"))
      (node (ref "U8") (pin "6") (pinfunction "E#_6") (pintype "input"))
      (node (ref "U8") (pin "8") (pinfunction "VSS_8") (pintype "input"))
    )
    (net (code "17") (name "Net-(C3-Pad2)") (class "Default")
      (node (ref "C3") (pin "2") (pinfunction "2_2") (pintype "input"))
      (node (ref "C7") (pin "2") (pinfunction "2_2") (pintype "input"))
      (node (ref "R19") (pin "1") (pinfunction "1_1") (pintype "input"))
    )
    (net (code "18") (name "Net-(C4-Pad2)") (class "Default")
      (node (ref "C4") (pin "2") (pinfunction "2_2") (pintype "input"))
      (node (ref "R21") (pin "2") (pinfunction "2_2") (pintype "input"))
      (node (ref "R22") (pin "1") (pinfunction "1_1") (pintype "input"))
    )
    (net (code "19") (name "Net-(C5-Pad2)") (class "Default")
      (node (ref "C5") (pin "2") (pinfunction "2_2") (pintype "input"))
      (node (ref "R20") (pin "2") (pinfunction "2_2") (pintype "input"))
      (node (ref "R21") (pin "1") (pinfunction "1_1") (pintype "input"))
    )
    (net (code "20") (name "Net-(C6-Pad2)") (class "Default")
      (node (ref "C6") (pin "2") (pinfunction "2_2") (pintype "input"))
      (node (ref "R19") (pin "2") (pinfunction "2_2") (pintype "input"))
      (node (ref "R20") (pin "1") (pinfunction "1_1") (pintype "input"))
    )
    (net (code "21") (name "Net-(C24-Pad1)") (class "Default")
      (node (ref "C24") (pin "1") (pinfunction "1_1") (pintype "input"))
      (node (ref "C25") (pin "2") (pinfunction "2_2") (pintype "input"))
      (node (ref "R54") (pin "2") (pinfunction "2_2") (pintype "input"))
      (node (ref "R55") (pin "1") (pinfunction "1_1") (pintype "input"))
      (node (ref "R56") (pin "2") (pinfunction "2_2") (pintype "input"))
      (node (ref "R57") (pin "2") (pinfunction "2_2") (pintype "input"))
    )
    (net (code "22") (name "Net-(C36-Pad2)") (class "Default")
      (node (ref "C36") (pin "2") (pinfunction "2_2") (pintype "input"))
      (node (ref "R65") (pin "1") (pinfunction "1_1") (pintype "input"))
    )
    (net (code "23") (name "Net-(C44-Pad1)") (class "Default")
      (node (ref "C44") (pin "1") (pinfunction "1_1") (pintype "input"))
      (node (ref "R28") (pin "2") (pinfunction "2_2") (pintype "input"))
      (node (ref "R31") (pin "1") (pinfunction "1_1") (pintype "input"))
    )
    (net (code "24") (name "Net-(C44-Pad2)") (class "Default")
      (node (ref "C44") (pin "2") (pinfunction "2_2") (pintype "input"))
      (node (ref "LP") (pin "1") (pinfunction "1_1") (pintype "unspecified"))
    )
    (net (code "25") (name "Net-(C45-Pad1)") (class "Default")
      (node (ref "C45") (pin "1") (pinfunction "1_1") (pintype "input"))
      (node (ref "R29") (pin "2") (pinfunction "2_2") (pintype "input"))
      (node (ref "R30") (pin "1") (pinfunction "1_1") (pintype "input"))
    )
    (net (code "26") (name "Net-(C45-Pad2)") (class "Default")
      (node (ref "C45") (pin "2") (pinfunction "2_2") (pintype "input"))
      (node (ref "HP") (pin "1") (pinfunction "1_1") (pintype "unspecified"))
    )
    (net (code "27") (name "Net-(D1-C)") (class "Default")
      (node (ref "D1") (pin "1") (pinfunction "C_1") (pintype "input"))
      (node (ref "L2") (pin "2") (pinfunction "2_2") (pintype "input"))
      (node (ref "U5") (pin "2") (pinfunction "OUTPUT_2") (pintype "input"))
    )
    (net (code "28") (name "Net-(D2-A)") (class "Default")
      (node (ref "D2") (pin "1") (pinfunction "A_1") (pintype "input"))
      (node (ref "Q4") (pin "1") (pinfunction "B_1") (pintype "input"))
      (node (ref "Q5") (pin "1") (pinfunction "B_1") (pintype "input"))
      (node (ref "R11") (pin "1") (pinfunction "1_1") (pintype "input"))
    )
    (net (code "29") (name "Net-(D2-C)") (class "Default")
      (node (ref "D2") (pin "2") (pinfunction "C_2") (pintype "input"))
      (node (ref "D3") (pin "1") (pinfunction "A_1") (pintype "input"))
      (node (ref "U1") (pin "7") (pinfunction "OUT2_7") (pintype "input"))
    )
    (net (code "30") (name "Net-(D3-C)") (class "Default")
      (node (ref "D3") (pin "2") (pinfunction "C_2") (pintype "input"))
      (node (ref "Q2") (pin "1") (pinfunction "B_1") (pintype "input"))
      (node (ref "Q3") (pin "1") (pinfunction "B_1") (pintype "input"))
      (node (ref "R12") (pin "2") (pinfunction "2_2") (pintype "input"))
    )
    (net (code "31") (name "Net-(D4-A)") (class "Default")
      (node (ref "C10") (pin "2") (pinfunction "2_2") (pintype "input"))
      (node (ref "C11") (pin "2") (pinfunction "2_2") (pintype "input"))
      (node (ref "D4") (pin "2") (pinfunction "A_2") (pintype "input"))
      (node (ref "D5") (pin "2") (pinfunction "A_2") (pintype "input"))
    )
    (net (code "32") (name "Net-(D4-K)") (class "Default")
      (node (ref "C10") (pin "1") (pinfunction "1_1") (pintype "input"))
      (node (ref "D12") (pin "2") (pinfunction "2_2") (pintype "input"))
      (node (ref "D4") (pin "1") (pinfunction "K_1") (pintype "input"))
      (node (ref "Q7") (pin "2") (pinfunction "S_2") (pintype "input"))
      (node (ref "R6") (pin "1") (pinfunction "1_1") (pintype "input"))
      (node (ref "R71") (pin "1") (pinfunction "1_1") (pintype "input"))
    )
    (net (code "33") (name "Net-(D5-K)") (class "Default")
      (node (ref "C11") (pin "1") (pinfunction "1_1") (pintype "input"))
      (node (ref "D5") (pin "1") (pinfunction "K_1") (pintype "input"))
      (node (ref "HC") (pin "1") (pinfunction "1_1") (pintype "unspecified"))
    )
    (net (code "34") (name "Net-(D6-C)") (class "Default")
      (node (ref "D6") (pin "2") (pinfunction "C_2") (pintype "input"))
      (node (ref "D7") (pin "1") (pinfunction "A_1") (pintype "input"))
      (node (ref "R30") (pin "2") (pinfunction "2_2") (pintype "input"))
      (node (ref "U2") (pin "3") (pinfunction "POS1_3") (pintype "input"))
    )
    (net (code "35") (name "Net-(D8-C)") (class "Default")
      (node (ref "D8") (pin "2") (pinfunction "C_2") (pintype "input"))
      (node (ref "D9") (pin "1") (pinfunction "A_1") (pintype "input"))
      (node (ref "R31") (pin "2") (pinfunction "2_2") (pintype "input"))
      (node (ref "U2") (pin "12") (pinfunction "POS4_12") (pintype "input"))
    )
    (net (code "36") (name "Net-(LCD1-DB4)") (class "Default")
      (node (ref "LCD1") (pin "11") (pinfunction "DB4_11") (pintype "input"))
      (node (ref "U32") (pin "2") (pinfunction "Q2_2") (pintype "input"))
    )
    (net (code "37") (name "Net-(LCD1-DB5)") (class "Default")
      (node (ref "LCD1") (pin "12") (pinfunction "DB5_12") (pintype "input"))
      (node (ref "U32") (pin "3") (pinfunction "Q3_3") (pintype "input"))
    )
    (net (code "38") (name "Net-(LCD1-DB6)") (class "Default")
      (node (ref "LCD1") (pin "13") (pinfunction "DB6_13") (pintype "input"))
      (node (ref "U32") (pin "4") (pinfunction "Q4_4") (pintype "input"))
    )
    (net (code "39") (name "Net-(LCD1-DB7)") (class "Default")
      (node (ref "LCD1") (pin "14") (pinfunction "DB7_14") (pintype "input"))
      (node (ref "U32") (pin "5") (pinfunction "Q5_5") (pintype "input"))
    )
    (net (code "40") (name "Net-(LCD1-E)") (class "Default")
      (node (ref "LCD1") (pin "6") (pinfunction "E_6") (pintype "input"))
      (node (ref "U32") (pin "1") (pinfunction "Q1_1") (pintype "input"))
    )
    (net (code "41") (name "Net-(LCD1-K)") (class "Default")
      (node (ref "LCD1") (pin "16") (pinfunction "K_16") (pintype "input"))
      (node (ref "R33") (pin "1") (pinfunction "1_1") (pintype "input"))
    )
    (net (code "42") (name "Net-(LCD1-RS)") (class "Default")
      (node (ref "LCD1") (pin "4") (pinfunction "RS_4") (pintype "input"))
      (node (ref "U32") (pin "15") (pinfunction "Q0_15") (pintype "input"))
    )
    (net (code "43") (name "Net-(LCD1-V0)") (class "Default")
      (node (ref "LCD1") (pin "3") (pinfunction "V0_3") (pintype "input"))
      (node (ref "R34") (pin "2") (pinfunction "2_2") (pintype "input"))
    )
    (net (code "44") (name "Net-(Q2-E)") (class "Default")
      (node (ref "Q2") (pin "2") (pinfunction "E_2") (pintype "input"))
      (node (ref "R9") (pin "1") (pinfunction "1_1") (pintype "input"))
    )
    (net (code "45") (name "Net-(Q3-E)") (class "Default")
      (node (ref "Q3") (pin "2") (pinfunction "E_2") (pintype "input"))
      (node (ref "R8") (pin "1") (pinfunction "1_1") (pintype "input"))
    )
    (net (code "46") (name "Net-(Q4-E)") (class "Default")
      (node (ref "Q4") (pin "2") (pinfunction "E_2") (pintype "input"))
      (node (ref "R10") (pin "2") (pinfunction "2_2") (pintype "input"))
    )
    (net (code "47") (name "Net-(Q5-E)") (class "Default")
      (node (ref "Q5") (pin "2") (pinfunction "E_2") (pintype "input"))
      (node (ref "R7") (pin "2") (pinfunction "2_2") (pintype "input"))
    )
    (net (code "48") (name "Net-(Q6-D)") (class "Default")
      (node (ref "Q6") (pin "3") (pinfunction "D_3") (pintype "input"))
      (node (ref "Q7") (pin "3") (pinfunction "D_3") (pintype "input"))
    )
    (net (code "49") (name "Net-(Q6-G)") (class "Default")
      (node (ref "Q6") (pin "1") (pinfunction "G_1") (pintype "input"))
      (node (ref "Q7") (pin "1") (pinfunction "G_1") (pintype "input"))
      (node (ref "U8") (pin "14") (pinfunction "ZA_14") (pintype "input"))
    )
    (net (code "50") (name "Net-(Q6-S)") (class "Default")
      (node (ref "Q6") (pin "2") (pinfunction "S_2") (pintype "input"))
      (node (ref "R5") (pin "1") (pinfunction "1_1") (pintype "input"))
      (node (ref "R69") (pin "1") (pinfunction "1_1") (pintype "input"))
      (node (ref "R71") (pin "2") (pinfunction "2_2") (pintype "input"))
    )
    (net (code "51") (name "Net-(R1-Pad2)") (class "Default")
      (node (ref "R1") (pin "2") (pinfunction "2_2") (pintype "input"))
      (node (ref "R2") (pin "2") (pinfunction "2_2") (pintype "input"))
      (node (ref "R34") (pin "1") (pinfunction "1_1") (pintype "input"))
    )
    (net (code "52") (name "Net-(R10-Pad1)") (class "Default")
      (node (ref "R10") (pin "1") (pinfunction "1_1") (pintype "input"))
      (node (ref "R3") (pin "1") (pinfunction "1_1") (pintype "input"))
      (node (ref "R69") (pin "2") (pinfunction "2_2") (pintype "input"))
      (node (ref "R7") (pin "1") (pinfunction "1_1") (pintype "input"))
      (node (ref "R8") (pin "2") (pinfunction "2_2") (pintype "input"))
      (node (ref "R9") (pin "2") (pinfunction "2_2") (pintype "input"))
    )
    (net (code "53") (name "Net-(U1-NEG1)") (class "Default")
      (node (ref "R13") (pin "2") (pinfunction "2_2") (pintype "input"))
      (node (ref "U1") (pin "1") (pinfunction "OUT1_1") (pintype "input"))
      (node (ref "U1") (pin "2") (pinfunction "NEG1_2") (pintype "input"))
    )
    (net (code "54") (name "Net-(U1-NEG2)") (class "Default")
      (node (ref "R13") (pin "1") (pinfunction "1_1") (pintype "input"))
      (node (ref "R17") (pin "2") (pinfunction "2_2") (pintype "input"))
      (node (ref "U1") (pin "6") (pinfunction "NEG2_6") (pintype "input"))
    )
    (net (code "55") (name "Net-(U1-NEG3)") (class "Default")
      (node (ref "R17") (pin "1") (pinfunction "1_1") (pintype "input"))
      (node (ref "U1") (pin "8") (pinfunction "OUT3_8") (pintype "input"))
      (node (ref "U1") (pin "9") (pinfunction "NEG3_9") (pintype "input"))
    )
    (net (code "56") (name "Net-(U1-NEG4)") (class "Default")
      (node (ref "R16") (pin "2") (pinfunction "2_2") (pintype "input"))
      (node (ref "U1") (pin "13") (pinfunction "NEG4_13") (pintype "input"))
      (node (ref "U1") (pin "14") (pinfunction "OUT4_14") (pintype "input"))
    )
    (net (code "57") (name "Net-(U1-POS1)") (class "Default")
      (node (ref "U1") (pin "3") (pinfunction "POS1_3") (pintype "input"))
      (node (ref "U8") (pin "4") (pinfunction "ZC_4") (pintype "input"))
    )
    (net (code "58") (name "Net-(U1-POS2)") (class "Default")
      (node (ref "R15") (pin "2") (pinfunction "2_2") (pintype "input"))
      (node (ref "R16") (pin "1") (pinfunction "1_1") (pintype "input"))
      (node (ref "U1") (pin "5") (pinfunction "POS2_5") (pintype "input"))
    )
    (net (code "59") (name "Net-(U1-POS3)") (class "Default")
      (node (ref "C3") (pin "1") (pinfunction "1_1") (pintype "input"))
      (node (ref "R18") (pin "2") (pinfunction "2_2") (pintype "input"))
      (node (ref "U1") (pin "10") (pinfunction "POS3_10") (pintype "input"))
    )
    (net (code "60") (name "Net-(U1-POS4)") (class "Default")
      (node (ref "U1") (pin "12") (pinfunction "POS4_12") (pintype "input"))
      (node (ref "U8") (pin "15") (pinfunction "ZB_15") (pintype "input"))
    )
    (net (code "61") (name "Net-(U2-NEG1)") (class "Default")
      (node (ref "R42") (pin "1") (pinfunction "1_1") (pintype "input"))
      (node (ref "U2") (pin "1") (pinfunction "OUT1_1") (pintype "input"))
      (node (ref "U2") (pin "2") (pinfunction "NEG1_2") (pintype "input"))
    )
    (net (code "62") (name "Net-(U2-NEG2)") (class "Default")
      (node (ref "C30") (pin "1") (pinfunction "1_1") (pintype "input"))
      (node (ref "R36") (pin "2") (pinfunction "2_2") (pintype "input"))
      (node (ref "R38") (pin "1") (pinfunction "1_1") (pintype "input"))
      (node (ref "R39") (pin "2") (pinfunction "2_2") (pintype "input"))
      (node (ref "U2") (pin "6") (pinfunction "NEG2_6") (pintype "input"))
    )
    (net (code "63") (name "Net-(U2-NEG3)") (class "Default")
      (node (ref "R37") (pin "1") (pinfunction "1_1") (pintype "input"))
      (node (ref "R42") (pin "2") (pinfunction "2_2") (pintype "input"))
      (node (ref "U2") (pin "9") (pinfunction "NEG3_9") (pintype "input"))
    )
    (net (code "64") (name "Net-(U2-NEG4)") (class "Default")
      (node (ref "R40") (pin "2") (pinfunction "2_2") (pintype "input"))
      (node (ref "U2") (pin "13") (pinfunction "NEG4_13") (pintype "input"))
      (node (ref "U2") (pin "14") (pinfunction "OUT4_14") (pintype "input"))
    )
    (net (code "65") (name "Net-(U2-OUT2)") (class "Default")
      (node (ref "C30") (pin "2") (pinfunction "2_2") (pintype "input"))
      (node (ref "R36") (pin "1") (pinfunction "1_1") (pintype "input"))
      (node (ref "R38") (pin "2") (pinfunction "2_2") (pintype "input"))
      (node (ref "R43") (pin "2") (pinfunction "2_2") (pintype "input"))
      (node (ref "R44") (pin "2") (pinfunction "2_2") (pintype "input"))
      (node (ref "U2") (pin "7") (pinfunction "OUT2_7") (pintype "input"))
      (node (ref "U3") (pin "1") (pinfunction "Y1B_1") (pintype "input"))
    )
    (net (code "66") (name "Net-(U2-OUT3)") (class "Default")
      (node (ref "R37") (pin "2") (pinfunction "2_2") (pintype "input"))
      (node (ref "R46") (pin "2") (pinfunction "2_2") (pintype "input"))
      (node (ref "R47") (pin "2") (pinfunction "2_2") (pintype "input"))
      (node (ref "U2") (pin "8") (pinfunction "OUT3_8") (pintype "input"))
      (node (ref "U3") (pin "3") (pinfunction "Y1C_3") (pintype "input"))
    )
    (net (code "67") (name "Net-(U2-POS2)") (class "Default")
      (node (ref "C31") (pin "2") (pinfunction "2_2") (pintype "input"))
      (node (ref "R63") (pin "2") (pinfunction "2_2") (pintype "input"))
      (node (ref "U2") (pin "5") (pinfunction "POS2_5") (pintype "input"))
    )
    (net (code "68") (name "Net-(U2-POS3)") (class "Default")
      (node (ref "R40") (pin "1") (pinfunction "1_1") (pintype "input"))
      (node (ref "R41") (pin "2") (pinfunction "2_2") (pintype "input"))
      (node (ref "U2") (pin "10") (pinfunction "POS3_10") (pintype "input"))
    )
    (net (code "69") (name "Net-(U3-Y0A)") (class "Default")
      (node (ref "R49") (pin "1") (pinfunction "1_1") (pintype "input"))
      (node (ref "R50") (pin "1") (pinfunction "1_1") (pintype "input"))
      (node (ref "R51") (pin "2") (pinfunction "2_2") (pintype "input"))
      (node (ref "U3") (pin "12") (pinfunction "Y0A_12") (pintype "input"))
    )
    (net (code "70") (name "Net-(U3-Y0B)") (class "Default")
      (node (ref "R43") (pin "1") (pinfunction "1_1") (pintype "input"))
      (node (ref "R44") (pin "1") (pinfunction "1_1") (pintype "input"))
      (node (ref "R45") (pin "2") (pinfunction "2_2") (pintype "input"))
      (node (ref "U3") (pin "2") (pinfunction "Y0B_2") (pintype "input"))
    )
    (net (code "71") (name "Net-(U3-Y0C)") (class "Default")
      (node (ref "R46") (pin "1") (pinfunction "1_1") (pintype "input"))
      (node (ref "R47") (pin "1") (pinfunction "1_1") (pintype "input"))
      (node (ref "R48") (pin "2") (pinfunction "2_2") (pintype "input"))
      (node (ref "U3") (pin "5") (pinfunction "Y0C_5") (pintype "input"))
    )
    (net (code "72") (name "Net-(U3-ZA)") (class "Default")
      (node (ref "C26") (pin "1") (pinfunction "1_1") (pintype "input"))
      (node (ref "U3") (pin "14") (pinfunction "ZA_14") (pintype "input"))
    )
    (net (code "73") (name "Net-(U3-ZB)") (class "Default")
      (node (ref "C27") (pin "1") (pinfunction "1_1") (pintype "input"))
      (node (ref "U3") (pin "15") (pinfunction "ZB_15") (pintype "input"))
    )
    (net (code "74") (name "Net-(U3-ZC)") (class "Default")
      (node (ref "C31") (pin "1") (pinfunction "1_1") (pintype "input"))
      (node (ref "U3") (pin "4") (pinfunction "ZC_4") (pintype "input"))
    )
    (net (code "75") (name "Net-(U5-ON{slash}OFF)") (class "Default")
      (node (ref "R64") (pin "2") (pinfunction "2_2") (pintype "input"))
      (node (ref "R65") (pin "2") (pinfunction "2_2") (pintype "input"))
      (node (ref "U5") (pin "5") (pinfunction "ON/OFF_5") (pintype "input"))
    )
    (net (code "76") (name "Net-(U6-BOOT0)") (class "Default")
      (node (ref "R35") (pin "1") (pinfunction "1_1") (pintype "input"))
      (node (ref "U6") (pin "1") (pinfunction "BOOT0_1") (pintype "input"))
    )
    (net (code "77") (name "Net-(U6-NRST)") (class "Default")
      (node (ref "C14") (pin "1") (pinfunction "1_1") (pintype "input"))
      (node (ref "U6") (pin "4") (pinfunction "NRST_4") (pintype "bidirectional"))
    )
    (net (code "78") (name "Net-(U6-PA6)") (class "Default")
      (node (ref "SW1") (pin "1") (pinfunction "1_1") (pintype "input"))
      (node (ref "SW1") (pin "2") (pinfunction "2_2") (pintype "input"))
      (node (ref "U6") (pin "12") (pinfunction "PA6_12") (pintype "bidirectional"))
    )
    (net (code "79") (name "Net-(U6-PA9)") (class "Default")
      (node (ref "SW2") (pin "1") (pinfunction "1_1") (pintype "input"))
      (node (ref "SW2") (pin "2") (pinfunction "2_2") (pintype "input"))
      (node (ref "U6") (pin "17") (pinfunction "PA9_17") (pintype "bidirectional"))
    )
    (net (code "80") (name "Net-(U6-PA13(SWDIO))") (class "Default")
      (node (ref "H5") (pin "2") (pinfunction "2_2") (pintype "input"))
      (node (ref "U6") (pin "19") (pinfunction "PA13(SWDIO)_19") (pintype "bidirectional"))
    )
    (net (code "81") (name "Net-(U6-PA14(SWCLK))") (class "Default")
      (node (ref "H5") (pin "1") (pinfunction "1_1") (pintype "input"))
      (node (ref "U6") (pin "20") (pinfunction "PA14(SWCLK)_20") (pintype "bidirectional"))
    )
    (net (code "82") (name "Net-(U6-PF0-OSC_IN(PF0))") (class "Default")
      (node (ref "C15") (pin "1") (pinfunction "1_1") (pintype "input"))
      (node (ref "U6") (pin "2") (pinfunction "PF0-OSC_IN(PF0)_2") (pintype "bidirectional"))
      (node (ref "X1") (pin "1") (pinfunction "OSC1_1") (pintype "input"))
    )
    (net (code "83") (name "Net-(U6-PF1-OSC_OUT(PF1))") (class "Default")
      (node (ref "C16") (pin "1") (pinfunction "1_1") (pintype "input"))
      (node (ref "U6") (pin "3") (pinfunction "PF1-OSC_OUT(PF1)_3") (pintype "bidirectional"))
      (node (ref "X1") (pin "2") (pinfunction "OSC2_2") (pintype "input"))
    )
    (net (code "84") (name "Net-(U6-VDDA)") (class "Default")
      (node (ref "C17") (pin "2") (pinfunction "2_2") (pintype "input"))
      (node (ref "L1") (pin "1") (pinfunction "1_1") (pintype "input"))
      (node (ref "U6") (pin "5") (pinfunction "VDDA_5") (pintype "input"))
    )
    (net (code "85") (name "Net-(U8-Y0A)") (class "Default")
      (node (ref "R23") (pin "2") (pinfunction "2_2") (pintype "input"))
      (node (ref "U8") (pin "12") (pinfunction "Y0A_12") (pintype "input"))
    )
    (net (code "86") (name "Net-(U8-Y0B)") (class "Default")
      (node (ref "R5") (pin "2") (pinfunction "2_2") (pintype "input"))
      (node (ref "U8") (pin "2") (pinfunction "Y0B_2") (pintype "input"))
      (node (ref "U8") (pin "3") (pinfunction "Y1C_3") (pintype "input"))
    )
    (net (code "87") (name "Net-(U8-Y0C)") (class "Default")
      (node (ref "R3") (pin "2") (pinfunction "2_2") (pintype "input"))
      (node (ref "U8") (pin "5") (pinfunction "Y0C_5") (pintype "input"))
    )
    (net (code "88") (name "Net-(U8-Y1A)") (class "Default")
      (node (ref "R24") (pin "2") (pinfunction "2_2") (pintype "input"))
      (node (ref "U8") (pin "13") (pinfunction "Y1A_13") (pintype "input"))
    )
    (net (code "89") (name "Net-(U8-Y1B)") (class "Default")
      (node (ref "R6") (pin "2") (pinfunction "2_2") (pintype "input"))
      (node (ref "U8") (pin "1") (pinfunction "Y1B_1") (pintype "input"))
    )
    (net (code "90") (name "Net-(U11A-IN1+)") (class "Default")
      (node (ref "C26") (pin "2") (pinfunction "2_2") (pintype "input"))
      (node (ref "R57") (pin "1") (pinfunction "1_1") (pintype "input"))
      (node (ref "U11") (pin "3") (pinfunction "IN1+_3") (pintype "input"))
    )
    (net (code "91") (name "Net-(U11A-IN1-)") (class "Default")
      (node (ref "C28") (pin "1") (pinfunction "1_1") (pintype "input"))
      (node (ref "R52") (pin "1") (pinfunction "1_1") (pintype "input"))
      (node (ref "R53") (pin "2") (pinfunction "2_2") (pintype "input"))
      (node (ref "R54") (pin "1") (pinfunction "1_1") (pintype "input"))
      (node (ref "U11") (pin "2") (pinfunction "IN1-_2") (pintype "input"))
    )
    (net (code "92") (name "Net-(U11A-OUT1)") (class "Default")
      (node (ref "C28") (pin "2") (pinfunction "2_2") (pintype "input"))
      (node (ref "R52") (pin "2") (pinfunction "2_2") (pintype "input"))
      (node (ref "R53") (pin "1") (pinfunction "1_1") (pintype "input"))
      (node (ref "R62") (pin "1") (pinfunction "1_1") (pintype "input"))
      (node (ref "U11") (pin "1") (pinfunction "OUT1_1") (pintype "output"))
    )
    (net (code "93") (name "Net-(U11B-IN2+)") (class "Default")
      (node (ref "C27") (pin "2") (pinfunction "2_2") (pintype "input"))
      (node (ref "R58") (pin "2") (pinfunction "2_2") (pintype "input"))
      (node (ref "U11") (pin "5") (pinfunction "IN2+_5") (pintype "input"))
    )
    (net (code "94") (name "Net-(U11B-IN2-)") (class "Default")
      (node (ref "C29") (pin "1") (pinfunction "1_1") (pintype "input"))
      (node (ref "R59") (pin "1") (pinfunction "1_1") (pintype "input"))
      (node (ref "R60") (pin "2") (pinfunction "2_2") (pintype "input"))
      (node (ref "R61") (pin "2") (pinfunction "2_2") (pintype "input"))
      (node (ref "U11") (pin "6") (pinfunction "IN2-_6") (pintype "input"))
    )
    (net (code "95") (name "Net-(U11B-OUT2)") (class "Default")
      (node (ref "C29") (pin "2") (pinfunction "2_2") (pintype "input"))
      (node (ref "R49") (pin "2") (pinfunction "2_2") (pintype "input"))
      (node (ref "R50") (pin "2") (pinfunction "2_2") (pintype "input"))
      (node (ref "R59") (pin "2") (pinfunction "2_2") (pintype "input"))
      (node (ref "R60") (pin "1") (pinfunction "1_1") (pintype "input"))
      (node (ref "U11") (pin "7") (pinfunction "OUT2_7") (pintype "output"))
      (node (ref "U3") (pin "13") (pinfunction "Y1A_13") (pintype "input"))
    )
    (net (code "96") (name "unconnected-(LCD1-DB0-Pad7)") (class "Default")
      (node (ref "LCD1") (pin "7") (pinfunction "DB0_7") (pintype "input+no_connect"))
    )
    (net (code "97") (name "unconnected-(LCD1-DB1-Pad8)") (class "Default")
      (node (ref "LCD1") (pin "8") (pinfunction "DB1_8") (pintype "input+no_connect"))
    )
    (net (code "98") (name "unconnected-(LCD1-DB2-Pad9)") (class "Default")
      (node (ref "LCD1") (pin "9") (pinfunction "DB2_9") (pintype "input+no_connect"))
    )
    (net (code "99") (name "unconnected-(LCD1-DB3-Pad10)") (class "Default")
      (node (ref "LCD1") (pin "10") (pinfunction "DB3_10") (pintype "input+no_connect"))
    )
    (net (code "100") (name "unconnected-(U32-Q6-Pad6)") (class "Default")
      (node (ref "U32") (pin "6") (pinfunction "Q6_6") (pintype "input"))
    )
    (net (code "101") (name "unconnected-(U32-Q7&apos;-Pad9)") (class "Default")
      (node (ref "U32") (pin "9") (pinfunction "Q7&apos;_9") (pintype "input"))
    )
    (net (code "102") (name "unconnected-(U32-Q7-Pad7)") (class "Default")
      (node (ref "U32") (pin "7") (pinfunction "Q7_7") (pintype "input"))
    )
  )
)
